# 3_Rotary_Encoder_Encoder.net
KiCad netlist of a schematic drawn in Altium Designer
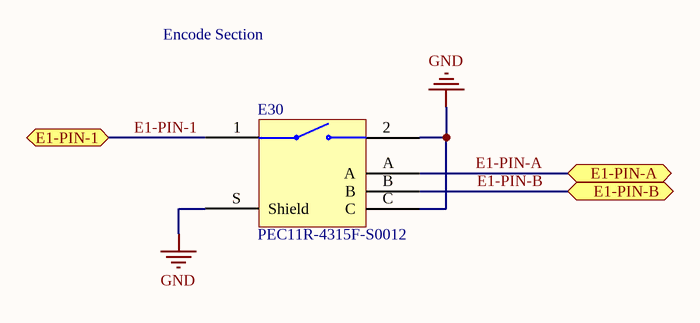
[diagram p0: 3_Rotary_Encoder_Encoder.SchDoc]

(export (version "E")
  (design (tool "Eeschema 10.0.6"))
  (components
    (comp (ref "E30")
      (value "PEC11R-4315F-S0012")
      (footprint "BOURNS PEC11R-4315F-S0012")
      (description "ROTARY ENCODER MECHANICAL 12PPR")
      (fields (field (name "MANUFACTURER") "Bourns Inc."))
      (libsource (lib "Rotary_Encoder") (part "BOURNS PEC11R-4315F-S0012"))
    )
  )
  (nets
    (net (code "1") (name "/E1-PIN-1") (class "Default")
      (node (ref "E30") (pin "1") (pinfunction "1_1") (pintype "passive"))
    )
    (net (code "2") (name "/E1-PIN-A") (class "Default")
      (node (ref "E30") (pin "A") (pinfunction "A_A") (pintype "passive"))
    )
    (net (code "3") (name "/E1-PIN-B") (class "Default")
      (node (ref "E30") (pin "B") (pinfunction "B_B") (pintype "passive"))
    )
    (net (code "4") (name "GND") (class "Default")
      (node (ref "E30") (pin "2") (pinfunction "2_2") (pintype "passive"))
      (node (ref "E30") (pin "C") (pinfunction "C_C") (pintype "passive"))
      (node (ref "E30") (pin "S") (pinfunction "Shield_S") (pintype "passive"))
    )
  )
)
